# schematic32MB.net
KiCad netlist of a schematic drawn in EasyEDA
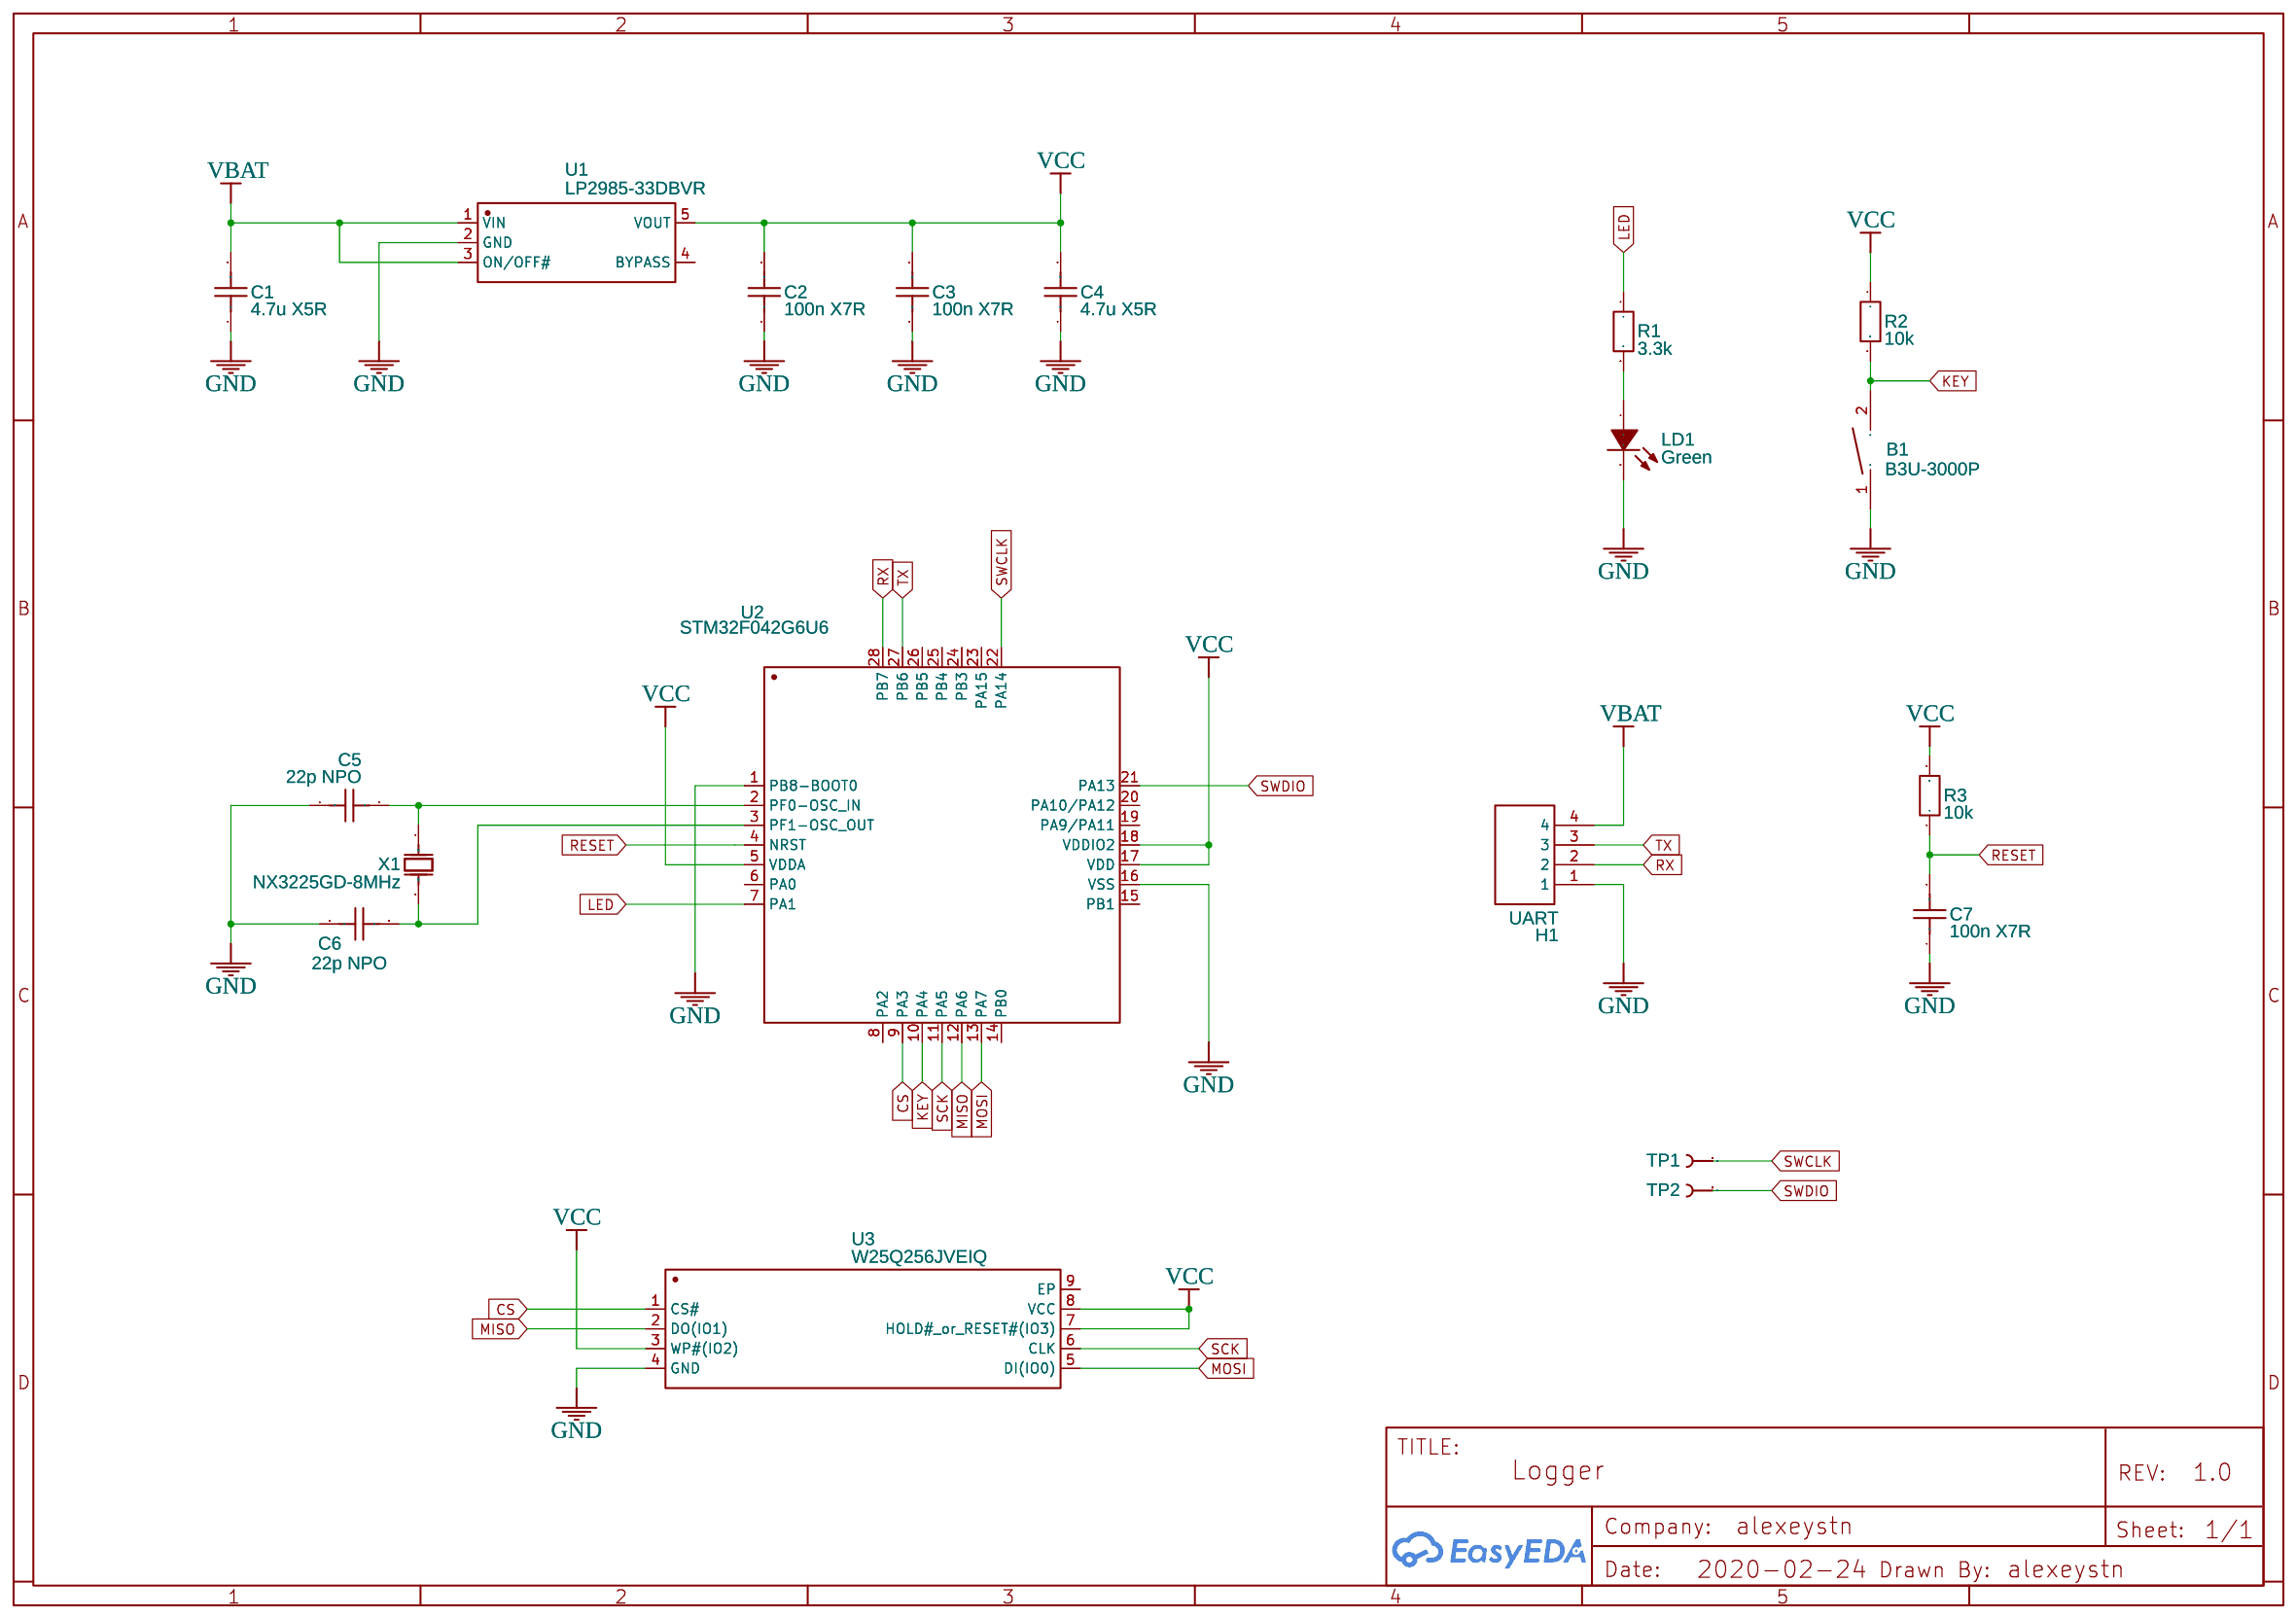
[diagram p0: schematic sheet]

(export (version "E")
  (design (tool "Eeschema 10.0.6"))
  (components
    (comp (ref "B1")
      (value "B3U-3000P")
      (fields
        (field (name "BOM_Manufacturer Part") "B3U-3000PM-B")
        (field (name "BOM_Supplier Part") "C306884")
      )
      (libsource (lib "") (part "B3U-3000PM-B"))
    )
    (comp (ref "C1") (value "4.7u X5R") (libsource (lib "") (part "Cap_0805_US")))
    (comp (ref "C2") (value "100n X7R") (libsource (lib "") (part "Cap_0805_US")))
    (comp (ref "C3") (value "100n X7R") (libsource (lib "") (part "Cap_0805_US")))
    (comp (ref "C4") (value "4.7u X5R") (libsource (lib "") (part "Cap_0805_US")))
    (comp (ref "C5") (value "22p NPO") (libsource (lib "") (part "Cap_0805_US_1")))
    (comp (ref "C6") (value "22p NPO") (libsource (lib "") (part "Cap_0805_US_1")))
    (comp (ref "C7") (value "100n X7R") (libsource (lib "") (part "Cap_0805_US")))
    (comp (ref "H1")
      (value "UART")
      (fields
        (field (name "BOM_Manufacturer Part") "220S-1*4P H=8.5MM Ytype Gold-plated")
        (field (name "BOM_Supplier Part") "C124413")
      )
      (libsource (lib "") (part "220S-1*4P H=8.5MM Ytype Gold-plated"))
    )
    (comp (ref "LD1")
      (value "Green")
      (fields
        (field (name "BOM_Manufacturer Part") "17-21SURC/S530-A2/TR8")
        (field (name "BOM_Supplier Part") "C131244")
      )
      (libsource (lib "") (part "17-21SURC/S530-A2/TR8"))
    )
    (comp (ref "R1") (value "3.3k") (libsource (lib "") (part "Res_0805(1/8W)_EU")))
    (comp (ref "R2") (value "10k") (libsource (lib "") (part "Res_0805(1/8W)_EU")))
    (comp (ref "R3") (value "10k") (libsource (lib "") (part "Res_0805(1/8W)_EU_1")))
    (comp (ref "TP1") (value "TEST-POINT3") (libsource (lib "") (part "TEST-POINT3")))
    (comp (ref "TP2") (value "TEST-POINT3") (libsource (lib "") (part "TEST-POINT3")))
    (comp (ref "U1")
      (value "LP2985-33DBVR")
      (fields (field (name "BOM_Supplier Part") "C95414"))
      (libsource (lib "") (part "LP2985-33DBVR"))
    )
    (comp (ref "U2")
      (value "STM32F042G6U6")
      (fields
        (field (name "BOM_Manufacturer Part") "STM32F042G4U6")
        (field (name "BOM_Supplier Part") "C88048")
      )
      (libsource (lib "") (part "STM32F042G4U6"))
    )
    (comp (ref "U3")
      (value "W25Q256JVEIQ")
      (fields (field (name "BOM_Supplier Part") "C2682312"))
      (libsource (lib "") (part "W25Q256JVEIQ"))
    )
    (comp (ref "X1") (value "NX3225GD-8MHz") (libsource (lib "") (part "NX3225GD-8MHZ-STD-CRA-3")))
  )
  (nets
    (net (code "1") (name "CS") (class "Default")
      (node (ref "U2") (pin "9") (pinfunction "PA3_9") (pintype "unspecified"))
      (node (ref "U3") (pin "1") (pinfunction "CS#_1") (pintype "unspecified"))
    )
    (net (code "2") (name "GND") (class "Default")
      (node (ref "B1") (pin "1") (pinfunction "1_1") (pintype "input"))
      (node (ref "C1") (pin "1") (pinfunction "1_1") (pintype "unspecified"))
      (node (ref "C2") (pin "1") (pinfunction "1_1") (pintype "unspecified"))
      (node (ref "C3") (pin "1") (pinfunction "1_1") (pintype "unspecified"))
      (node (ref "C4") (pin "1") (pinfunction "1_1") (pintype "unspecified"))
      (node (ref "C5") (pin "1") (pinfunction "1_1") (pintype "unspecified"))
      (node (ref "C6") (pin "1") (pinfunction "1_1") (pintype "unspecified"))
      (node (ref "C7") (pin "1") (pinfunction "1_1") (pintype "unspecified"))
      (node (ref "H1") (pin "1") (pinfunction "1_1") (pintype "unspecified"))
      (node (ref "LD1") (pin "2") (pinfunction "K_2") (pintype "unspecified"))
      (node (ref "U1") (pin "2") (pinfunction "GND_2") (pintype "unspecified"))
      (node (ref "U2") (pin "1") (pinfunction "PB8-BOOT0_1") (pintype "unspecified"))
      (node (ref "U2") (pin "16") (pinfunction "VSS_16") (pintype "unspecified"))
      (node (ref "U3") (pin "4") (pinfunction "GND_4") (pintype "unspecified"))
    )
    (net (code "3") (name "KEY") (class "Default")
      (node (ref "B1") (pin "2") (pinfunction "2_2") (pintype "input"))
      (node (ref "R2") (pin "2") (pinfunction "2_2") (pintype "unspecified"))
      (node (ref "U2") (pin "10") (pinfunction "PA4_10") (pintype "unspecified"))
    )
    (net (code "4") (name "LED") (class "Default")
      (node (ref "R1") (pin "1") (pinfunction "1_1") (pintype "unspecified"))
      (node (ref "U2") (pin "7") (pinfunction "PA1_7") (pintype "unspecified"))
    )
    (net (code "5") (name "MISO") (class "Default")
      (node (ref "U2") (pin "12") (pinfunction "PA6_12") (pintype "unspecified"))
      (node (ref "U3") (pin "2") (pinfunction "DO(IO1)_2") (pintype "unspecified"))
    )
    (net (code "6") (name "MOSI") (class "Default")
      (node (ref "U2") (pin "13") (pinfunction "PA7_13") (pintype "unspecified"))
      (node (ref "U3") (pin "5") (pinfunction "DI(IO0)_5") (pintype "unspecified"))
    )
    (net (code "7") (name "Net-(LD1-A)") (class "Default")
      (node (ref "LD1") (pin "1") (pinfunction "A_1") (pintype "unspecified"))
      (node (ref "R1") (pin "2") (pinfunction "2_2") (pintype "unspecified"))
    )
    (net (code "8") (name "Net-(U2-PF0-OSC_IN)") (class "Default")
      (node (ref "C5") (pin "2") (pinfunction "2_2") (pintype "unspecified"))
      (node (ref "U2") (pin "2") (pinfunction "PF0-OSC_IN_2") (pintype "unspecified"))
      (node (ref "X1") (pin "1") (pinfunction "OSC1_1") (pintype "input"))
    )
    (net (code "9") (name "Net-(U2-PF1-OSC_OUT)") (class "Default")
      (node (ref "C6") (pin "2") (pinfunction "2_2") (pintype "unspecified"))
      (node (ref "U2") (pin "3") (pinfunction "PF1-OSC_OUT_3") (pintype "unspecified"))
      (node (ref "X1") (pin "2") (pinfunction "OSC2_2") (pintype "input"))
    )
    (net (code "10") (name "RESET") (class "Default")
      (node (ref "C7") (pin "2") (pinfunction "2_2") (pintype "unspecified"))
      (node (ref "R3") (pin "1") (pinfunction "1_1") (pintype "unspecified"))
      (node (ref "U2") (pin "4") (pinfunction "NRST_4") (pintype "unspecified"))
    )
    (net (code "11") (name "RX") (class "Default")
      (node (ref "H1") (pin "2") (pinfunction "2_2") (pintype "unspecified"))
      (node (ref "U2") (pin "28") (pinfunction "PB7_28") (pintype "unspecified"))
    )
    (net (code "12") (name "SCK") (class "Default")
      (node (ref "U2") (pin "11") (pinfunction "PA5_11") (pintype "unspecified"))
      (node (ref "U3") (pin "6") (pinfunction "CLK_6") (pintype "unspecified"))
    )
    (net (code "13") (name "SWCLK") (class "Default")
      (node (ref "TP1") (pin "P$1") (pinfunction "1_P$1") (pintype "unspecified"))
      (node (ref "U2") (pin "22") (pinfunction "PA14_22") (pintype "unspecified"))
    )
    (net (code "14") (name "SWDIO") (class "Default")
      (node (ref "TP2") (pin "P$1") (pinfunction "1_P$1") (pintype "unspecified"))
      (node (ref "U2") (pin "21") (pinfunction "PA13_21") (pintype "unspecified"))
    )
    (net (code "15") (name "TX") (class "Default")
      (node (ref "H1") (pin "3") (pinfunction "3_3") (pintype "unspecified"))
      (node (ref "U2") (pin "27") (pinfunction "PB6_27") (pintype "unspecified"))
    )
    (net (code "16") (name "VBAT") (class "Default")
      (node (ref "C1") (pin "2") (pinfunction "2_2") (pintype "unspecified"))
      (node (ref "H1") (pin "4") (pinfunction "4_4") (pintype "unspecified"))
      (node (ref "U1") (pin "1") (pinfunction "VIN_1") (pintype "unspecified"))
      (node (ref "U1") (pin "3") (pinfunction "ON/OFF#_3") (pintype "unspecified"))
    )
    (net (code "17") (name "VCC") (class "Default")
      (node (ref "C2") (pin "2") (pinfunction "2_2") (pintype "unspecified"))
      (node (ref "C3") (pin "2") (pinfunction "2_2") (pintype "unspecified"))
      (node (ref "C4") (pin "2") (pinfunction "2_2") (pintype "unspecified"))
      (node (ref "R2") (pin "1") (pinfunction "1_1") (pintype "unspecified"))
      (node (ref "R3") (pin "2") (pinfunction "2_2") (pintype "unspecified"))
      (node (ref "U1") (pin "5") (pinfunction "VOUT_5") (pintype "unspecified"))
      (node (ref "U2") (pin "17") (pinfunction "VDD_17") (pintype "unspecified"))
      (node (ref "U2") (pin "18") (pinfunction "VDDIO2_18") (pintype "unspecified"))
      (node (ref "U2") (pin "5") (pinfunction "VDDA_5") (pintype "unspecified"))
      (node (ref "U3") (pin "3") (pinfunction "WP#(IO2)_3") (pintype "unspecified"))
      (node (ref "U3") (pin "7") (pinfunction "HOLD#_or_RESET#(IO3)_7") (pintype "unspecified"))
      (node (ref "U3") (pin "8") (pinfunction "VCC_8") (pintype "unspecified"))
    )
    (net (code "18") (name "unconnected-(U1-BYPASS-Pad4)") (class "Default")
      (node (ref "U1") (pin "4") (pinfunction "BYPASS_4") (pintype "unspecified"))
    )
    (net (code "19") (name "unconnected-(U2-PA0-Pad6)") (class "Default")
      (node (ref "U2") (pin "6") (pinfunction "PA0_6") (pintype "unspecified"))
    )
    (net (code "20") (name "unconnected-(U2-PA2-Pad8)") (class "Default")
      (node (ref "U2") (pin "8") (pinfunction "PA2_8") (pintype "unspecified"))
    )
    (net (code "21") (name "unconnected-(U2-PA9{slash}PA11-Pad19)") (class "Default")
      (node (ref "U2") (pin "19") (pinfunction "PA9/PA11_19") (pintype "unspecified"))
    )
    (net (code "22") (name "unconnected-(U2-PA10{slash}PA12-Pad20)") (class "Default")
      (node (ref "U2") (pin "20") (pinfunction "PA10/PA12_20") (pintype "unspecified"))
    )
    (net (code "23") (name "unconnected-(U2-PA15-Pad23)") (class "Default")
      (node (ref "U2") (pin "23") (pinfunction "PA15_23") (pintype "unspecified"))
    )
    (net (code "24") (name "unconnected-(U2-PB0-Pad14)") (class "Default")
      (node (ref "U2") (pin "14") (pinfunction "PB0_14") (pintype "unspecified"))
    )
    (net (code "25") (name "unconnected-(U2-PB1-Pad15)") (class "Default")
      (node (ref "U2") (pin "15") (pinfunction "PB1_15") (pintype "unspecified"))
    )
    (net (code "26") (name "unconnected-(U2-PB3-Pad24)") (class "Default")
      (node (ref "U2") (pin "24") (pinfunction "PB3_24") (pintype "unspecified"))
    )
    (net (code "27") (name "unconnected-(U2-PB4-Pad25)") (class "Default")
      (node (ref "U2") (pin "25") (pinfunction "PB4_25") (pintype "unspecified"))
    )
    (net (code "28") (name "unconnected-(U2-PB5-Pad26)") (class "Default")
      (node (ref "U2") (pin "26") (pinfunction "PB5_26") (pintype "unspecified"))
    )
    (net (code "29") (name "unconnected-(U3-EP-Pad9)") (class "Default")
      (node (ref "U3") (pin "9") (pinfunction "EP_9") (pintype "unspecified"))
    )
  )
)
